# sch.net
KiCad netlist of a schematic drawn in EAGLE
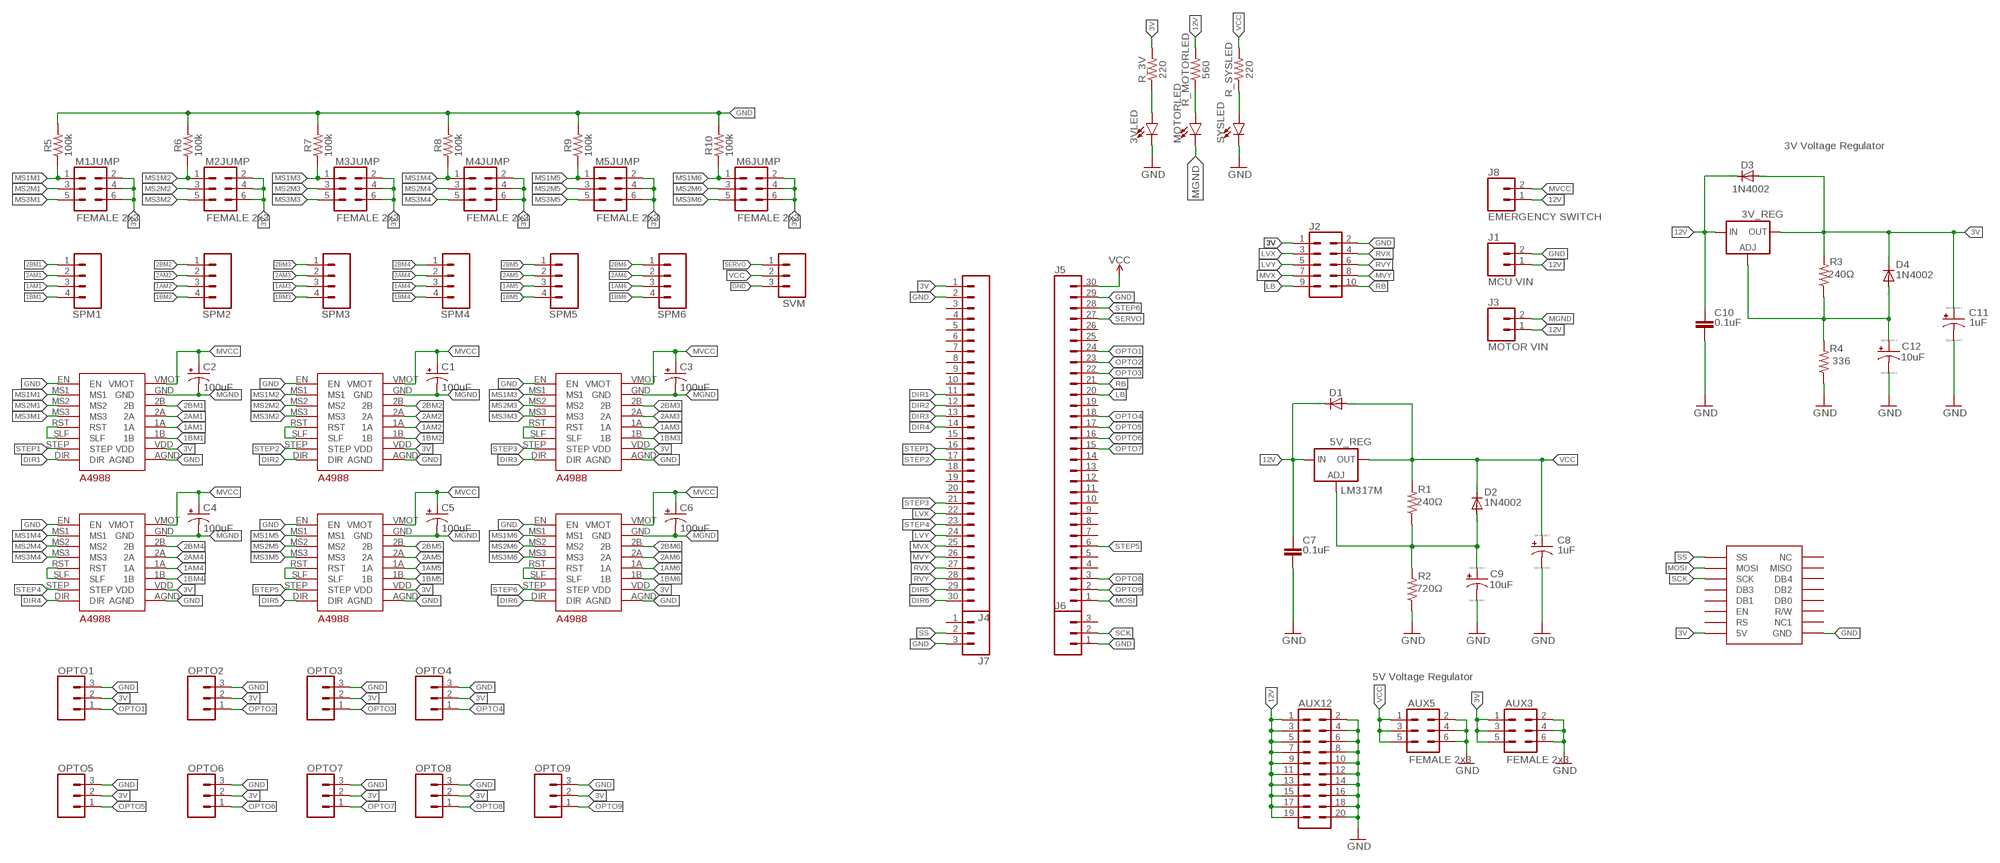
[diagram p0: schematic, sheet 1]

(export (version "E")
  (design (tool "Eeschema 10.0.6"))
  (components
    (comp (ref "3VLED")
      (value "LED1206")
      (footprint "eagle-import:LED-1206")
      (libsource (lib "eagle-import") (part "LED1206"))
    )
    (comp (ref "3V_REG")
      (value "LM317MBSTT3")
      (footprint "eagle-import:SOT223")
      (fields (field (name "PARTNUMBER") "LM317M"))
      (libsource (lib "eagle-import") (part "LM317?MBSTT3"))
    )
    (comp (ref "5V_REG")
      (value "LM317MBSTT3")
      (footprint "eagle-import:SOT223")
      (fields (field (name "PARTNUMBER") "LM317M"))
      (libsource (lib "eagle-import") (part "LM317?MBSTT3"))
    )
    (comp (ref "AUX3")
      (value "FEMALE 2x3")
      (footprint "eagle-import:2X3")
      (libsource (lib "eagle-import") (part "CONN_03X2FEMALE"))
    )
    (comp (ref "AUX5")
      (value "FEMALE 2x3")
      (footprint "eagle-import:2X3")
      (libsource (lib "eagle-import") (part "CONN_03X2FEMALE"))
    )
    (comp (ref "AUX12")
      (value "CONN_10X2")
      (footprint "eagle-import:2X10")
      (libsource (lib "eagle-import") (part "CONN_10X2"))
    )
    (comp (ref "C1")
      (value "100uF")
      (footprint "eagle-import:CPOL-RADIAL-2.5MM-6.5MM")
      (libsource (lib "eagle-import") (part "100UF-POLAR-RADIAL-2.5MM-25V-20%"))
    )
    (comp (ref "C2")
      (value "100uF")
      (footprint "eagle-import:CPOL-RADIAL-2.5MM-6.5MM")
      (libsource (lib "eagle-import") (part "100UF-POLAR-RADIAL-2.5MM-25V-20%"))
    )
    (comp (ref "C3")
      (value "100uF")
      (footprint "eagle-import:CPOL-RADIAL-2.5MM-6.5MM")
      (libsource (lib "eagle-import") (part "100UF-POLAR-RADIAL-2.5MM-25V-20%"))
    )
    (comp (ref "C4")
      (value "100uF")
      (footprint "eagle-import:CPOL-RADIAL-2.5MM-6.5MM")
      (libsource (lib "eagle-import") (part "100UF-POLAR-RADIAL-2.5MM-25V-20%"))
    )
    (comp (ref "C5")
      (value "100uF")
      (footprint "eagle-import:CPOL-RADIAL-2.5MM-6.5MM")
      (libsource (lib "eagle-import") (part "100UF-POLAR-RADIAL-2.5MM-25V-20%"))
    )
    (comp (ref "C6")
      (value "100uF")
      (footprint "eagle-import:CPOL-RADIAL-2.5MM-6.5MM")
      (libsource (lib "eagle-import") (part "100UF-POLAR-RADIAL-2.5MM-25V-20%"))
    )
    (comp (ref "C7")
      (value "0.1uF")
      (footprint "eagle-import:C075-052X106")
      (libsource (lib "eagle-import") (part "C-EU075-052X106"))
    )
    (comp (ref "C8")
      (value "1uF")
      (footprint "eagle-import:085CS_1AR")
      (libsource (lib "eagle-import") (part "CPOL-US085CS-1AR"))
    )
    (comp (ref "C9")
      (value "10uF")
      (footprint "eagle-import:085CS_1AR")
      (libsource (lib "eagle-import") (part "CPOL-US085CS-1AR"))
    )
    (comp (ref "C10")
      (value "0.1uF")
      (footprint "eagle-import:C075-052X106")
      (libsource (lib "eagle-import") (part "C-EU075-052X106"))
    )
    (comp (ref "C11")
      (value "1uF")
      (footprint "eagle-import:085CS_1AR")
      (libsource (lib "eagle-import") (part "CPOL-US085CS-1AR"))
    )
    (comp (ref "C12")
      (value "10uF")
      (footprint "eagle-import:085CS_1AR")
      (libsource (lib "eagle-import") (part "CPOL-US085CS-1AR"))
    )
    (comp (ref "D1")
      (value "1N4002")
      (footprint "eagle-import:DO41-10")
      (libsource (lib "eagle-import") (part "1N4004"))
    )
    (comp (ref "D2")
      (value "1N4002")
      (footprint "eagle-import:DO41-10")
      (libsource (lib "eagle-import") (part "1N4004"))
    )
    (comp (ref "D3")
      (value "1N4002")
      (footprint "eagle-import:DO41-10")
      (libsource (lib "eagle-import") (part "1N4004"))
    )
    (comp (ref "D4")
      (value "1N4002")
      (footprint "eagle-import:DO41-10")
      (libsource (lib "eagle-import") (part "1N4004"))
    )
    (comp (ref "J1")
      (value "MCU VIN")
      (footprint "eagle-import:SCREWTERMINAL-3.5MM-2")
      (libsource (lib "eagle-import") (part "CONN_023.5MM"))
    )
    (comp (ref "J2")
      (value "CONN_05X2SHD")
      (footprint "eagle-import:2X5-SHROUDED")
      (libsource (lib "eagle-import") (part "CONN_05X2SHD"))
    )
    (comp (ref "J3")
      (value "MOTOR VIN")
      (footprint "eagle-import:SCREWTERMINAL-3.5MM-2")
      (libsource (lib "eagle-import") (part "CONN_023.5MM"))
    )
    (comp (ref "J4")
      (value "CONN_30")
      (footprint "eagle-import:1X30")
      (libsource (lib "eagle-import") (part "CONN_30"))
    )
    (comp (ref "J5")
      (value "CONN_30")
      (footprint "eagle-import:1X30")
      (libsource (lib "eagle-import") (part "CONN_30"))
    )
    (comp (ref "J6")
      (value "CONN_03")
      (footprint "eagle-import:1X03")
      (libsource (lib "eagle-import") (part "SparkFun-Connectors_513_CONN_03"))
    )
    (comp (ref "J7")
      (value "CONN_03")
      (footprint "eagle-import:1X03")
      (libsource (lib "eagle-import") (part "SparkFun-Connectors_513_CONN_03"))
    )
    (comp (ref "J8")
      (value "EMERGENCY SWITCH")
      (footprint "eagle-import:SCREWTERMINAL-3.5MM-2")
      (libsource (lib "eagle-import") (part "CONN_023.5MM"))
    )
    (comp (ref "M1")
      (value "A4988_BREAK_OUTTROUGH_HOLE")
      (footprint "eagle-import:A4988_BREAK_OUT")
      (libsource (lib "eagle-import") (part "A4988_BREAK_OUTTROUGH_HOLE"))
    )
    (comp (ref "M1JUMP")
      (value "FEMALE 2x3")
      (footprint "eagle-import:2X3")
      (libsource (lib "eagle-import") (part "CONN_03X2FEMALE"))
    )
    (comp (ref "M2")
      (value "A4988_BREAK_OUTTROUGH_HOLE")
      (footprint "eagle-import:A4988_BREAK_OUT")
      (libsource (lib "eagle-import") (part "A4988_BREAK_OUTTROUGH_HOLE"))
    )
    (comp (ref "M2JUMP")
      (value "FEMALE 2x3")
      (footprint "eagle-import:2X3")
      (libsource (lib "eagle-import") (part "CONN_03X2FEMALE"))
    )
    (comp (ref "M3")
      (value "A4988_BREAK_OUTTROUGH_HOLE")
      (footprint "eagle-import:A4988_BREAK_OUT")
      (libsource (lib "eagle-import") (part "A4988_BREAK_OUTTROUGH_HOLE"))
    )
    (comp (ref "M3JUMP")
      (value "FEMALE 2x3")
      (footprint "eagle-import:2X3")
      (libsource (lib "eagle-import") (part "CONN_03X2FEMALE"))
    )
    (comp (ref "M4")
      (value "A4988_BREAK_OUTTROUGH_HOLE")
      (footprint "eagle-import:A4988_BREAK_OUT")
      (libsource (lib "eagle-import") (part "A4988_BREAK_OUTTROUGH_HOLE"))
    )
    (comp (ref "M4JUMP")
      (value "FEMALE 2x3")
      (footprint "eagle-import:2X3")
      (libsource (lib "eagle-import") (part "CONN_03X2FEMALE"))
    )
    (comp (ref "M5")
      (value "A4988_BREAK_OUTTROUGH_HOLE")
      (footprint "eagle-import:A4988_BREAK_OUT")
      (libsource (lib "eagle-import") (part "A4988_BREAK_OUTTROUGH_HOLE"))
    )
    (comp (ref "M5JUMP")
      (value "FEMALE 2x3")
      (footprint "eagle-import:2X3")
      (libsource (lib "eagle-import") (part "CONN_03X2FEMALE"))
    )
    (comp (ref "M6")
      (value "A4988_BREAK_OUTTROUGH_HOLE")
      (footprint "eagle-import:A4988_BREAK_OUT")
      (libsource (lib "eagle-import") (part "A4988_BREAK_OUTTROUGH_HOLE"))
    )
    (comp (ref "M6JUMP")
      (value "FEMALE 2x3")
      (footprint "eagle-import:2X3")
      (libsource (lib "eagle-import") (part "CONN_03X2FEMALE"))
    )
    (comp (ref "MOTORLED")
      (value "LED1206")
      (footprint "eagle-import:LED-1206")
      (libsource (lib "eagle-import") (part "LED1206"))
    )
    (comp (ref "OPTO1")
      (value "455-1750-1-ND")
      (footprint "eagle-import:1X03")
      (libsource (lib "eagle-import") (part "CONN_03"))
    )
    (comp (ref "OPTO2")
      (value "455-1750-1-ND")
      (footprint "eagle-import:1X03")
      (libsource (lib "eagle-import") (part "CONN_03"))
    )
    (comp (ref "OPTO3")
      (value "455-1750-1-ND")
      (footprint "eagle-import:1X03")
      (libsource (lib "eagle-import") (part "CONN_03"))
    )
    (comp (ref "OPTO4")
      (value "455-1750-1-ND")
      (footprint "eagle-import:1X03")
      (libsource (lib "eagle-import") (part "CONN_03"))
    )
    (comp (ref "OPTO5")
      (value "455-1750-1-ND")
      (footprint "eagle-import:1X03")
      (libsource (lib "eagle-import") (part "CONN_03"))
    )
    (comp (ref "OPTO6")
      (value "455-1750-1-ND")
      (footprint "eagle-import:1X03")
      (libsource (lib "eagle-import") (part "CONN_03"))
    )
    (comp (ref "OPTO7")
      (value "455-1750-1-ND")
      (footprint "eagle-import:1X03")
      (libsource (lib "eagle-import") (part "CONN_03"))
    )
    (comp (ref "OPTO8")
      (value "455-1750-1-ND")
      (footprint "eagle-import:1X03")
      (libsource (lib "eagle-import") (part "CONN_03"))
    )
    (comp (ref "OPTO9")
      (value "455-1750-1-ND")
      (footprint "eagle-import:1X03")
      (libsource (lib "eagle-import") (part "CONN_03"))
    )
    (comp (ref "R1")
      (value "240Ω")
      (footprint "eagle-import:M0805")
      (libsource (lib "eagle-import") (part "R-US_M0805"))
    )
    (comp (ref "R2")
      (value "720Ω")
      (footprint "eagle-import:M0805")
      (libsource (lib "eagle-import") (part "R-US_M0805"))
    )
    (comp (ref "R3")
      (value "240Ω")
      (footprint "eagle-import:M0805")
      (libsource (lib "eagle-import") (part "R-US_M0805"))
    )
    (comp (ref "R4")
      (value "336")
      (footprint "eagle-import:M0805")
      (libsource (lib "eagle-import") (part "R-US_M0805"))
    )
    (comp (ref "R5")
      (value "100k")
      (footprint "eagle-import:0603")
      (libsource (lib "eagle-import") (part "100KOHM-0603-1/10W-1%"))
    )
    (comp (ref "R6")
      (value "100k")
      (footprint "eagle-import:0603")
      (libsource (lib "eagle-import") (part "100KOHM-0603-1/10W-1%"))
    )
    (comp (ref "R7")
      (value "100k")
      (footprint "eagle-import:0603")
      (libsource (lib "eagle-import") (part "100KOHM-0603-1/10W-1%"))
    )
    (comp (ref "R8")
      (value "100k")
      (footprint "eagle-import:0603")
      (libsource (lib "eagle-import") (part "100KOHM-0603-1/10W-1%"))
    )
    (comp (ref "R9")
      (value "100k")
      (footprint "eagle-import:0603")
      (libsource (lib "eagle-import") (part "100KOHM-0603-1/10W-1%"))
    )
    (comp (ref "R10")
      (value "100k")
      (footprint "eagle-import:0603")
      (libsource (lib "eagle-import") (part "100KOHM-0603-1/10W-1%"))
    )
    (comp (ref "R_3V")
      (value "220")
      (footprint "eagle-import:0603")
      (libsource (lib "eagle-import") (part "680OHM-0603-1/10W-5%"))
    )
    (comp (ref "R_MOTORLED")
      (value "560")
      (footprint "eagle-import:0603")
      (libsource (lib "eagle-import") (part "680OHM-0603-1/10W-5%"))
    )
    (comp (ref "R_SYSLED")
      (value "220")
      (footprint "eagle-import:0603")
      (libsource (lib "eagle-import") (part "680OHM-0603-1/10W-5%"))
    )
    (comp (ref "SPM1")
      (value "CONN_04")
      (footprint "eagle-import:1X04")
      (libsource (lib "eagle-import") (part "CONN_04"))
    )
    (comp (ref "SPM2")
      (value "CONN_04")
      (footprint "eagle-import:1X04")
      (libsource (lib "eagle-import") (part "CONN_04"))
    )
    (comp (ref "SPM3")
      (value "CONN_04")
      (footprint "eagle-import:1X04")
      (libsource (lib "eagle-import") (part "CONN_04"))
    )
    (comp (ref "SPM4")
      (value "CONN_04")
      (footprint "eagle-import:1X04")
      (libsource (lib "eagle-import") (part "CONN_04"))
    )
    (comp (ref "SPM5")
      (value "CONN_04")
      (footprint "eagle-import:1X04")
      (libsource (lib "eagle-import") (part "CONN_04"))
    )
    (comp (ref "SPM6")
      (value "CONN_04")
      (footprint "eagle-import:1X04")
      (libsource (lib "eagle-import") (part "CONN_04"))
    )
    (comp (ref "SVM")
      (value "CONN_03")
      (footprint "eagle-import:1X03")
      (libsource (lib "eagle-import") (part "SparkFun-Connectors_513_CONN_03"))
    )
    (comp (ref "SYSLED")
      (value "LED1206")
      (footprint "eagle-import:LED-1206")
      (libsource (lib "eagle-import") (part "LED1206"))
    )
    (comp (ref "U$7")
      (value "LCD-BREAKOUT")
      (footprint "eagle-import:LCD_BREAKOUT")
      (libsource (lib "eagle-import") (part "LCD-BREAKOUT"))
    )
  )
  (nets
    (net (code "1") (name "1AM1") (class "Default")
      (node (ref "M1") (pin "1A") (pinfunction "1A_1A") (pintype "bidirectional"))
      (node (ref "SPM1") (pin "3") (pinfunction "3_3") (pintype "passive"))
    )
    (net (code "2") (name "1AM2") (class "Default")
      (node (ref "M2") (pin "1A") (pinfunction "1A_1A") (pintype "bidirectional"))
      (node (ref "SPM2") (pin "3") (pinfunction "3_3") (pintype "passive"))
    )
    (net (code "3") (name "1AM3") (class "Default")
      (node (ref "M3") (pin "1A") (pinfunction "1A_1A") (pintype "bidirectional"))
      (node (ref "SPM3") (pin "3") (pinfunction "3_3") (pintype "passive"))
    )
    (net (code "4") (name "1AM4") (class "Default")
      (node (ref "M4") (pin "1A") (pinfunction "1A_1A") (pintype "bidirectional"))
      (node (ref "SPM4") (pin "3") (pinfunction "3_3") (pintype "passive"))
    )
    (net (code "5") (name "1AM5") (class "Default")
      (node (ref "M5") (pin "1A") (pinfunction "1A_1A") (pintype "bidirectional"))
      (node (ref "SPM5") (pin "3") (pinfunction "3_3") (pintype "passive"))
    )
    (net (code "6") (name "1AM6") (class "Default")
      (node (ref "M6") (pin "1A") (pinfunction "1A_1A") (pintype "bidirectional"))
      (node (ref "SPM6") (pin "3") (pinfunction "3_3") (pintype "passive"))
    )
    (net (code "7") (name "1BM1") (class "Default")
      (node (ref "M1") (pin "1B") (pinfunction "1B_1B") (pintype "bidirectional"))
      (node (ref "SPM1") (pin "4") (pinfunction "4_4") (pintype "passive"))
    )
    (net (code "8") (name "1BM2") (class "Default")
      (node (ref "M2") (pin "1B") (pinfunction "1B_1B") (pintype "bidirectional"))
      (node (ref "SPM2") (pin "4") (pinfunction "4_4") (pintype "passive"))
    )
    (net (code "9") (name "1BM3") (class "Default")
      (node (ref "M3") (pin "1B") (pinfunction "1B_1B") (pintype "bidirectional"))
      (node (ref "SPM3") (pin "4") (pinfunction "4_4") (pintype "passive"))
    )
    (net (code "10") (name "1BM4") (class "Default")
      (node (ref "M4") (pin "1B") (pinfunction "1B_1B") (pintype "bidirectional"))
      (node (ref "SPM4") (pin "4") (pinfunction "4_4") (pintype "passive"))
    )
    (net (code "11") (name "1BM5") (class "Default")
      (node (ref "M5") (pin "1B") (pinfunction "1B_1B") (pintype "bidirectional"))
      (node (ref "SPM5") (pin "4") (pinfunction "4_4") (pintype "passive"))
    )
    (net (code "12") (name "1BM6") (class "Default")
      (node (ref "M6") (pin "1B") (pinfunction "1B_1B") (pintype "bidirectional"))
      (node (ref "SPM6") (pin "4") (pinfunction "4_4") (pintype "passive"))
    )
    (net (code "13") (name "2AM1") (class "Default")
      (node (ref "M1") (pin "2A") (pinfunction "2A_2A") (pintype "bidirectional"))
      (node (ref "SPM1") (pin "2") (pinfunction "2_2") (pintype "passive"))
    )
    (net (code "14") (name "2AM2") (class "Default")
      (node (ref "M2") (pin "2A") (pinfunction "2A_2A") (pintype "bidirectional"))
      (node (ref "SPM2") (pin "2") (pinfunction "2_2") (pintype "passive"))
    )
    (net (code "15") (name "2AM3") (class "Default")
      (node (ref "M3") (pin "2A") (pinfunction "2A_2A") (pintype "bidirectional"))
      (node (ref "SPM3") (pin "2") (pinfunction "2_2") (pintype "passive"))
    )
    (net (code "16") (name "2AM4") (class "Default")
      (node (ref "M4") (pin "2A") (pinfunction "2A_2A") (pintype "bidirectional"))
      (node (ref "SPM4") (pin "2") (pinfunction "2_2") (pintype "passive"))
    )
    (net (code "17") (name "2AM5") (class "Default")
      (node (ref "M5") (pin "2A") (pinfunction "2A_2A") (pintype "bidirectional"))
      (node (ref "SPM5") (pin "2") (pinfunction "2_2") (pintype "passive"))
    )
    (net (code "18") (name "2AM6") (class "Default")
      (node (ref "M6") (pin "2A") (pinfunction "2A_2A") (pintype "bidirectional"))
      (node (ref "SPM6") (pin "2") (pinfunction "2_2") (pintype "passive"))
    )
    (net (code "19") (name "2BM1") (class "Default")
      (node (ref "M1") (pin "2B") (pinfunction "2B_2B") (pintype "bidirectional"))
      (node (ref "SPM1") (pin "1") (pinfunction "1_1") (pintype "passive"))
    )
    (net (code "20") (name "2BM2") (class "Default")
      (node (ref "M2") (pin "2B") (pinfunction "2B_2B") (pintype "bidirectional"))
      (node (ref "SPM2") (pin "1") (pinfunction "1_1") (pintype "passive"))
    )
    (net (code "21") (name "2BM3") (class "Default")
      (node (ref "M3") (pin "2B") (pinfunction "2B_2B") (pintype "bidirectional"))
      (node (ref "SPM3") (pin "1") (pinfunction "1_1") (pintype "passive"))
    )
    (net (code "22") (name "2BM4") (class "Default")
      (node (ref "M4") (pin "2B") (pinfunction "2B_2B") (pintype "bidirectional"))
      (node (ref "SPM4") (pin "1") (pinfunction "1_1") (pintype "passive"))
    )
    (net (code "23") (name "2BM5") (class "Default")
      (node (ref "M5") (pin "2B") (pinfunction "2B_2B") (pintype "bidirectional"))
      (node (ref "SPM5") (pin "1") (pinfunction "1_1") (pintype "passive"))
    )
    (net (code "24") (name "2BM6") (class "Default")
      (node (ref "M6") (pin "2B") (pinfunction "2B_2B") (pintype "bidirectional"))
      (node (ref "SPM6") (pin "1") (pinfunction "1_1") (pintype "passive"))
    )
    (net (code "25") (name "3V") (class "Default")
      (node (ref "3V_REG") (pin "4") (pinfunction "OUT_4") (pintype "passive"))
      (node (ref "AUX3") (pin "1") (pinfunction "1_1") (pintype "bidirectional"))
      (node (ref "AUX3") (pin "3") (pinfunction "3_3") (pintype "bidirectional"))
      (node (ref "AUX3") (pin "5") (pinfunction "5_5") (pintype "bidirectional"))
      (node (ref "C11") (pin "+") (pinfunction "+_+") (pintype "passive"))
      (node (ref "D3") (pin "A") (pinfunction "A_A") (pintype "passive"))
      (node (ref "D4") (pin "C") (pinfunction "C_C") (pintype "passive"))
      (node (ref "J2") (pin "1") (pinfunction "1_1") (pintype "passive"))
      (node (ref "J4") (pin "1") (pinfunction "1_1") (pintype "passive"))
      (node (ref "M1") (pin "VDD") (pinfunction "VDD_VDD") (pintype "bidirectional"))
      (node (ref "M1JUMP") (pin "2") (pinfunction "2_2") (pintype "bidirectional"))
      (node (ref "M1JUMP") (pin "4") (pinfunction "4_4") (pintype "bidirectional"))
      (node (ref "M1JUMP") (pin "6") (pinfunction "6_6") (pintype "bidirectional"))
      (node (ref "M2") (pin "VDD") (pinfunction "VDD_VDD") (pintype "bidirectional"))
      (node (ref "M2JUMP") (pin "2") (pinfunction "2_2") (pintype "bidirectional"))
      (node (ref "M2JUMP") (pin "4") (pinfunction "4_4") (pintype "bidirectional"))
      (node (ref "M2JUMP") (pin "6") (pinfunction "6_6") (pintype "bidirectional"))
      (node (ref "M3") (pin "VDD") (pinfunction "VDD_VDD") (pintype "bidirectional"))
      (node (ref "M3JUMP") (pin "2") (pinfunction "2_2") (pintype "bidirectional"))
      (node (ref "M3JUMP") (pin "4") (pinfunction "4_4") (pintype "bidirectional"))
      (node (ref "M3JUMP") (pin "6") (pinfunction "6_6") (pintype "bidirectional"))
      (node (ref "M4") (pin "VDD") (pinfunction "VDD_VDD") (pintype "bidirectional"))
      (node (ref "M4JUMP") (pin "2") (pinfunction "2_2") (pintype "bidirectional"))
      (node (ref "M4JUMP") (pin "4") (pinfunction "4_4") (pintype "bidirectional"))
      (node (ref "M4JUMP") (pin "6") (pinfunction "6_6") (pintype "bidirectional"))
      (node (ref "M5") (pin "VDD") (pinfunction "VDD_VDD") (pintype "bidirectional"))
      (node (ref "M5JUMP") (pin "2") (pinfunction "2_2") (pintype "bidirectional"))
      (node (ref "M5JUMP") (pin "4") (pinfunction "4_4") (pintype "bidirectional"))
      (node (ref "M5JUMP") (pin "6") (pinfunction "6_6") (pintype "bidirectional"))
      (node (ref "M6") (pin "VDD") (pinfunction "VDD_VDD") (pintype "bidirectional"))
      (node (ref "M6JUMP") (pin "2") (pinfunction "2_2") (pintype "bidirectional"))
      (node (ref "M6JUMP") (pin "4") (pinfunction "4_4") (pintype "bidirectional"))
      (node (ref "M6JUMP") (pin "6") (pinfunction "6_6") (pintype "bidirectional"))
      (node (ref "OPTO1") (pin "2") (pinfunction "2_2") (pintype "passive"))
      (node (ref "OPTO2") (pin "2") (pinfunction "2_2") (pintype "passive"))
      (node (ref "OPTO3") (pin "2") (pinfunction "2_2") (pintype "passive"))
      (node (ref "OPTO4") (pin "2") (pinfunction "2_2") (pintype "passive"))
      (node (ref "OPTO5") (pin "2") (pinfunction "2_2") (pintype "passive"))
      (node (ref "OPTO6") (pin "2") (pinfunction "2_2") (pintype "passive"))
      (node (ref "OPTO7") (pin "2") (pinfunction "2_2") (pintype "passive"))
      (node (ref "OPTO8") (pin "2") (pinfunction "2_2") (pintype "passive"))
      (node (ref "OPTO9") (pin "2") (pinfunction "2_2") (pintype "passive"))
      (node (ref "R3") (pin "2") (pinfunction "2_2") (pintype "passive"))
      (node (ref "R_3V") (pin "2") (pinfunction "2_2") (pintype "passive"))
      (node (ref "U$7") (pin "P$2") (pinfunction "5V_P$2") (pintype "bidirectional"))
    )
    (net (code "26") (name "12V") (class "Default")
      (node (ref "3V_REG") (pin "3") (pinfunction "IN_3") (pintype "input"))
      (node (ref "5V_REG") (pin "3") (pinfunction "IN_3") (pintype "input"))
      (node (ref "AUX12") (pin "1") (pinfunction "1_1") (pintype "passive"))
      (node (ref "AUX12") (pin "11") (pinfunction "11_11") (pintype "passive"))
      (node (ref "AUX12") (pin "13") (pinfunction "13_13") (pintype "passive"))
      (node (ref "AUX12") (pin "15") (pinfunction "15_15") (pintype "passive"))
      (node (ref "AUX12") (pin "17") (pinfunction "17_17") (pintype "passive"))
      (node (ref "AUX12") (pin "19") (pinfunction "19_19") (pintype "passive"))
      (node (ref "AUX12") (pin "3") (pinfunction "3_3") (pintype "passive"))
      (node (ref "AUX12") (pin "5") (pinfunction "5_5") (pintype "passive"))
      (node (ref "AUX12") (pin "7") (pinfunction "7_7") (pintype "passive"))
      (node (ref "AUX12") (pin "9") (pinfunction "9_9") (pintype "passive"))
      (node (ref "C10") (pin "1") (pinfunction "1_1") (pintype "passive"))
      (node (ref "C7") (pin "1") (pinfunction "1_1") (pintype "passive"))
      (node (ref "D1") (pin "C") (pinfunction "C_C") (pintype "passive"))
      (node (ref "D3") (pin "C") (pinfunction "C_C") (pintype "passive"))
      (node (ref "J1") (pin "1") (pinfunction "1_1") (pintype "passive"))
      (node (ref "J3") (pin "1") (pinfunction "1_1") (pintype "passive"))
      (node (ref "J8") (pin "1") (pinfunction "1_1") (pintype "passive"))
      (node (ref "R_MOTORLED") (pin "2") (pinfunction "2_2") (pintype "passive"))
    )
    (net (code "27") (name "DIR1") (class "Default")
      (node (ref "J4") (pin "11") (pinfunction "11_11") (pintype "passive"))
      (node (ref "M1") (pin "DIR") (pinfunction "DIR_DIR") (pintype "bidirectional"))
    )
    (net (code "28") (name "DIR2") (class "Default")
      (node (ref "J4") (pin "12") (pinfunction "12_12") (pintype "passive"))
      (node (ref "M2") (pin "DIR") (pinfunction "DIR_DIR") (pintype "bidirectional"))
    )
    (net (code "29") (name "DIR3") (class "Default")
      (node (ref "J4") (pin "13") (pinfunction "13_13") (pintype "passive"))
      (node (ref "M3") (pin "DIR") (pinfunction "DIR_DIR") (pintype "bidirectional"))
    )
    (net (code "30") (name "DIR4") (class "Default")
      (node (ref "J4") (pin "14") (pinfunction "14_14") (pintype "passive"))
      (node (ref "M4") (pin "DIR") (pinfunction "DIR_DIR") (pintype "bidirectional"))
    )
    (net (code "31") (name "DIR5") (class "Default")
      (node (ref "J4") (pin "29") (pinfunction "29_29") (pintype "passive"))
      (node (ref "M5") (pin "DIR") (pinfunction "DIR_DIR") (pintype "bidirectional"))
    )
    (net (code "32") (name "DIR6") (class "Default")
      (node (ref "J4") (pin "30") (pinfunction "30_30") (pintype "passive"))
      (node (ref "M6") (pin "DIR") (pinfunction "DIR_DIR") (pintype "bidirectional"))
    )
    (net (code "33") (name "GND") (class "Default")
      (node (ref "3VLED") (pin "C") (pinfunction "C_C") (pintype "passive"))
      (node (ref "AUX12") (pin "10") (pinfunction "10_10") (pintype "passive"))
      (node (ref "AUX12") (pin "12") (pinfunction "12_12") (pintype "passive"))
      (node (ref "AUX12") (pin "14") (pinfunction "14_14") (pintype "passive"))
      (node (ref "AUX12") (pin "16") (pinfunction "16_16") (pintype "passive"))
      (node (ref "AUX12") (pin "18") (pinfunction "18_18") (pintype "passive"))
      (node (ref "AUX12") (pin "2") (pinfunction "2_2") (pintype "passive"))
      (node (ref "AUX12") (pin "20") (pinfunction "20_20") (pintype "passive"))
      (node (ref "AUX12") (pin "4") (pinfunction "4_4") (pintype "passive"))
      (node (ref "AUX12") (pin "6") (pinfunction "6_6") (pintype "passive"))
      (node (ref "AUX12") (pin "8") (pinfunction "8_8") (pintype "passive"))
      (node (ref "AUX3") (pin "2") (pinfunction "2_2") (pintype "bidirectional"))
      (node (ref "AUX3") (pin "4") (pinfunction "4_4") (pintype "bidirectional"))
      (node (ref "AUX3") (pin "6") (pinfunction "6_6") (pintype "bidirectional"))
      (node (ref "AUX5") (pin "2") (pinfunction "2_2") (pintype "bidirectional"))
      (node (ref "AUX5") (pin "4") (pinfunction "4_4") (pintype "bidirectional"))
      (node (ref "AUX5") (pin "6") (pinfunction "6_6") (pintype "bidirectional"))
      (node (ref "C10") (pin "2") (pinfunction "2_2") (pintype "passive"))
      (node (ref "C11") (pin "-") (pinfunction "-_-") (pintype "passive"))
      (node (ref "C12") (pin "-") (pinfunction "-_-") (pintype "passive"))
      (node (ref "C7") (pin "2") (pinfunction "2_2") (pintype "passive"))
      (node (ref "C8") (pin "-") (pinfunction "-_-") (pintype "passive"))
      (node (ref "C9") (pin "-") (pinfunction "-_-") (pintype "passive"))
      (node (ref "J1") (pin "2") (pinfunction "2_2") (pintype "passive"))
      (node (ref "J2") (pin "2") (pinfunction "2_2") (pintype "passive"))
      (node (ref "J4") (pin "2") (pinfunction "2_2") (pintype "passive"))
      (node (ref "J5") (pin "29") (pinfunction "29_29") (pintype "passive"))
      (node (ref "J6") (pin "1") (pinfunction "1_1") (pintype "passive"))
      (node (ref "J7") (pin "3") (pinfunction "3_3") (pintype "passive"))
      (node (ref "M1") (pin "AGND") (pinfunction "AGND_AGND") (pintype "bidirectional"))
      (node (ref "M1") (pin "EN") (pinfunction "EN_EN") (pintype "bidirectional"))
      (node (ref "M2") (pin "AGND") (pinfunction "AGND_AGND") (pintype "bidirectional"))
      (node (ref "M2") (pin "EN") (pinfunction "EN_EN") (pintype "bidirectional"))
      (node (ref "M3") (pin "AGND") (pinfunction "AGND_AGND") (pintype "bidirectional"))
      (node (ref "M3") (pin "EN") (pinfunction "EN_EN") (pintype "bidirectional"))
      (node (ref "M4") (pin "AGND") (pinfunction "AGND_AGND") (pintype "bidirectional"))
      (node (ref "M4") (pin "EN") (pinfunction "EN_EN") (pintype "bidirectional"))
      (node (ref "M5") (pin "AGND") (pinfunction "AGND_AGND") (pintype "bidirectional"))
      (node (ref "M5") (pin "EN") (pinfunction "EN_EN") (pintype "bidirectional"))
      (node (ref "M6") (pin "AGND") (pinfunction "AGND_AGND") (pintype "bidirectional"))
      (node (ref "M6") (pin "EN") (pinfunction "EN_EN") (pintype "bidirectional"))
      (node (ref "OPTO1") (pin "3") (pinfunction "3_3") (pintype "passive"))
      (node (ref "OPTO2") (pin "3") (pinfunction "3_3") (pintype "passive"))
      (node (ref "OPTO3") (pin "3") (pinfunction "3_3") (pintype "passive"))
      (node (ref "OPTO4") (pin "3") (pinfunction "3_3") (pintype "passive"))
      (node (ref "OPTO5") (pin "3") (pinfunction "3_3") (pintype "passive"))
      (node (ref "OPTO6") (pin "3") (pinfunction "3_3") (pintype "passive"))
      (node (ref "OPTO7") (pin "3") (pinfunction "3_3") (pintype "passive"))
      (node (ref "OPTO8") (pin "3") (pinfunction "3_3") (pintype "passive"))
      (node (ref "OPTO9") (pin "3") (pinfunction "3_3") (pintype "passive"))
      (node (ref "R10") (pin "2") (pinfunction "2_2") (pintype "passive"))
      (node (ref "R2") (pin "1") (pinfunction "1_1") (pintype "passive"))
      (node (ref "R4") (pin "1") (pinfunction "1_1") (pintype "passive"))
      (node (ref "R5") (pin "2") (pinfunction "2_2") (pintype "passive"))
      (node (ref "R6") (pin "2") (pinfunction "2_2") (pintype "passive"))
      (node (ref "R7") (pin "2") (pinfunction "2_2") (pintype "passive"))
      (node (ref "R8") (pin "2") (pinfunction "2_2") (pintype "passive"))
      (node (ref "R9") (pin "2") (pinfunction "2_2") (pintype "passive"))
      (node (ref "SVM") (pin "3") (pinfunction "3_3") (pintype "passive"))
      (node (ref "SYSLED") (pin "C") (pinfunction "C_C") (pintype "passive"))
      (node (ref "U$7") (pin "P$1") (pinfunction "GND_P$1") (pintype "bidirectional"))
    )
    (net (code "34") (name "LB") (class "Default")
      (node (ref "J2") (pin "9") (pinfunction "9_9") (pintype "passive"))
      (node (ref "J5") (pin "20") (pinfunction "20_20") (pintype "passive"))
    )
    (net (code "35") (name "LVX") (class "Default")
      (node (ref "J2") (pin "3") (pinfunction "3_3") (pintype "passive"))
      (node (ref "J4") (pin "22") (pinfunction "22_22") (pintype "passive"))
    )
    (net (code "36") (name "LVY") (class "Default")
      (node (ref "J2") (pin "5") (pinfunction "5_5") (pintype "passive"))
      (node (ref "J4") (pin "24") (pinfunction "24_24") (pintype "passive"))
    )
    (net (code "37") (name "MGND") (class "Default")
      (node (ref "C1") (pin "2") (pinfunction "-_2") (pintype "passive"))
      (node (ref "C2") (pin "2") (pinfunction "-_2") (pintype "passive"))
      (node (ref "C3") (pin "2") (pinfunction "-_2") (pintype "passive"))
      (node (ref "C4") (pin "2") (pinfunction "-_2") (pintype "passive"))
      (node (ref "C5") (pin "2") (pinfunction "-_2") (pintype "passive"))
      (node (ref "C6") (pin "2") (pinfunction "-_2") (pintype "passive"))
      (node (ref "J3") (pin "2") (pinfunction "2_2") (pintype "passive"))
      (node (ref "M1") (pin "GND") (pinfunction "GND_GND") (pintype "bidirectional"))
      (node (ref "M2") (pin "GND") (pinfunction "GND_GND") (pintype "bidirectional"))
      (node (ref "M3") (pin "GND") (pinfunction "GND_GND") (pintype "bidirectional"))
      (node (ref "M4") (pin "GND") (pinfunction "GND_GND") (pintype "bidirectional"))
      (node (ref "M5") (pin "GND") (pinfunction "GND_GND") (pintype "bidirectional"))
      (node (ref "M6") (pin "GND") (pinfunction "GND_GND") (pintype "bidirectional"))
      (node (ref "MOTORLED") (pin "C") (pinfunction "C_C") (pintype "passive"))
    )
    (net (code "38") (name "MOSI") (class "Default")
      (node (ref "J5") (pin "1") (pinfunction "1_1") (pintype "passive"))
      (node (ref "U$7") (pin "P$14") (pinfunction "MOSI_P$14") (pintype "bidirectional"))
    )
    (net (code "39") (name "MS1M1") (class "Default")
      (node (ref "M1") (pin "MS1") (pinfunction "MS1_MS1") (pintype "bidirectional"))
      (node (ref "M1JUMP") (pin "1") (pinfunction "1_1") (pintype "bidirectional"))
      (node (ref "R5") (pin "1") (pinfunction "1_1") (pintype "passive"))
    )
    (net (code "40") (name "MS1M2") (class "Default")
      (node (ref "M2") (pin "MS1") (pinfunction "MS1_MS1") (pintype "bidirectional"))
      (node (ref "M2JUMP") (pin "1") (pinfunction "1_1") (pintype "bidirectional"))
      (node (ref "R6") (pin "1") (pinfunction "1_1") (pintype "passive"))
    )
    (net (code "41") (name "MS1M3") (class "Default")
      (node (ref "M3") (pin "MS1") (pinfunction "MS1_MS1") (pintype "bidirectional"))
      (node (ref "M3JUMP") (pin "1") (pinfunction "1_1") (pintype "bidirectional"))
      (node (ref "R7") (pin "1") (pinfunction "1_1") (pintype "passive"))
    )
    (net (code "42") (name "MS1M4") (class "Default")
      (node (ref "M4") (pin "MS1") (pinfunction "MS1_MS1") (pintype "bidirectional"))
      (node (ref "M4JUMP") (pin "1") (pinfunction "1_1") (pintype "bidirectional"))
      (node (ref "R8") (pin "1") (pinfunction "1_1") (pintype "passive"))
    )
    (net (code "43") (name "MS1M5") (class "Default")
      (node (ref "M5") (pin "MS1") (pinfunction "MS1_MS1") (pintype "bidirectional"))
      (node (ref "M5JUMP") (pin "1") (pinfunction "1_1") (pintype "bidirectional"))
      (node (ref "R9") (pin "1") (pinfunction "1_1") (pintype "passive"))
    )
    (net (code "44") (name "MS1M6") (class "Default")
      (node (ref "M6") (pin "MS1") (pinfunction "MS1_MS1") (pintype "bidirectional"))
      (node (ref "M6JUMP") (pin "1") (pinfunction "1_1") (pintype "bidirectional"))
      (node (ref "R10") (pin "1") (pinfunction "1_1") (pintype "passive"))
    )
    (net (code "45") (name "MS2M1") (class "Default")
      (node (ref "M1") (pin "MS2") (pinfunction "MS2_MS2") (pintype "bidirectional"))
      (node (ref "M1JUMP") (pin "3") (pinfunction "3_3") (pintype "bidirectional"))
    )
    (net (code "46") (name "MS2M2") (class "Default")
      (node (ref "M2") (pin "MS2") (pinfunction "MS2_MS2") (pintype "bidirectional"))
      (node (ref "M2JUMP") (pin "3") (pinfunction "3_3") (pintype "bidirectional"))
    )
    (net (code "47") (name "MS2M3") (class "Default")
      (node (ref "M3") (pin "MS2") (pinfunction "MS2_MS2") (pintype "bidirectional"))
      (node (ref "M3JUMP") (pin "3") (pinfunction "3_3") (pintype "bidirectional"))
    )
    (net (code "48") (name "MS2M4") (class "Default")
      (node (ref "M4") (pin "MS2") (pinfunction "MS2_MS2") (pintype "bidirectional"))
      (node (ref "M4JUMP") (pin "3") (pinfunction "3_3") (pintype "bidirectional"))
    )
    (net (code "49") (name "MS2M5") (class "Default")
      (node (ref "M5") (pin "MS2") (pinfunction "MS2_MS2") (pintype "bidirectional"))
      (node (ref "M5JUMP") (pin "3") (pinfunction "3_3") (pintype "bidirectional"))
    )
    (net (code "50") (name "MS2M6") (class "Default")
      (node (ref "M6") (pin "MS2") (pinfunction "MS2_MS2") (pintype "bidirectional"))
      (node (ref "M6JUMP") (pin "3") (pinfunction "3_3") (pintype "bidirectional"))
    )
    (net (code "51") (name "MS3M1") (class "Default")
      (node (ref "M1") (pin "MS3") (pinfunction "MS3_MS3") (pintype "bidirectional"))
      (node (ref "M1JUMP") (pin "5") (pinfunction "5_5") (pintype "bidirectional"))
    )
    (net (code "52") (name "MS3M2") (class "Default")
      (node (ref "M2") (pin "MS3") (pinfunction "MS3_MS3") (pintype "bidirectional"))
      (node (ref "M2JUMP") (pin "5") (pinfunction "5_5") (pintype "bidirectional"))
    )
    (net (code "53") (name "MS3M3") (class "Default")
      (node (ref "M3") (pin "MS3") (pinfunction "MS3_MS3") (pintype "bidirectional"))
      (node (ref "M3JUMP") (pin "5") (pinfunction "5_5") (pintype "bidirectional"))
    )
    (net (code "54") (name "MS3M4") (class "Default")
      (node (ref "M4") (pin "MS3") (pinfunction "MS3_MS3") (pintype "bidirectional"))
      (node (ref "M4JUMP") (pin "5") (pinfunction "5_5") (pintype "bidirectional"))
    )
    (net (code "55") (name "MS3M5") (class "Default")
      (node (ref "M5") (pin "MS3") (pinfunction "MS3_MS3") (pintype "bidirectional"))
      (node (ref "M5JUMP") (pin "5") (pinfunction "5_5") (pintype "bidirectional"))
    )
    (net (code "56") (name "MS3M6") (class "Default")
      (node (ref "M6") (pin "MS3") (pinfunction "MS3_MS3") (pintype "bidirectional"))
      (node (ref "M6JUMP") (pin "5") (pinfunction "5_5") (pintype "bidirectional"))
    )
    (net (code "57") (name "MVCC") (class "Default")
      (node (ref "C1") (pin "1") (pinfunction "+_1") (pintype "passive"))
      (node (ref "C2") (pin "1") (pinfunction "+_1") (pintype "passive"))
      (node (ref "C3") (pin "1") (pinfunction "+_1") (pintype "passive"))
      (node (ref "C4") (pin "1") (pinfunction "+_1") (pintype "passive"))
      (node (ref "C5") (pin "1") (pinfunction "+_1") (pintype "passive"))
      (node (ref "C6") (pin "1") (pinfunction "+_1") (pintype "passive"))
      (node (ref "J8") (pin "2") (pinfunction "2_2") (pintype "passive"))
      (node (ref "M1") (pin "VMOT") (pinfunction "VMOT_VMOT") (pintype "bidirectional"))
      (node (ref "M2") (pin "VMOT") (pinfunction "VMOT_VMOT") (pintype "bidirectional"))
      (node (ref "M3") (pin "VMOT") (pinfunction "VMOT_VMOT") (pintype "bidirectional"))
      (node (ref "M4") (pin "VMOT") (pinfunction "VMOT_VMOT") (pintype "bidirectional"))
      (node (ref "M5") (pin "VMOT") (pinfunction "VMOT_VMOT") (pintype "bidirectional"))
      (node (ref "M6") (pin "VMOT") (pinfunction "VMOT_VMOT") (pintype "bidirectional"))
    )
    (net (code "58") (name "MVX") (class "Default")
      (node (ref "J2") (pin "7") (pinfunction "7_7") (pintype "passive"))
      (node (ref "J4") (pin "25") (pinfunction "25_25") (pintype "passive"))
    )
    (net (code "59") (name "MVY") (class "Default")
      (node (ref "J2") (pin "8") (pinfunction "8_8") (pintype "passive"))
      (node (ref "J4") (pin "26") (pinfunction "26_26") (pintype "passive"))
    )
    (net (code "60") (name "Net-(3VLED-PadA)") (class "Default")
      (node (ref "3VLED") (pin "A") (pinfunction "A_A") (pintype "passive"))
      (node (ref "R_3V") (pin "1") (pinfunction "1_1") (pintype "passive"))
    )
    (net (code "61") (name "Net-(3V_REG-ADJ)") (class "Default")
      (node (ref "3V_REG") (pin "1") (pinfunction "ADJ_1") (pintype "input"))
      (node (ref "C12") (pin "+") (pinfunction "+_+") (pintype "passive"))
      (node (ref "D4") (pin "A") (pinfunction "A_A") (pintype "passive"))
      (node (ref "R3") (pin "1") (pinfunction "1_1") (pintype "passive"))
      (node (ref "R4") (pin "2") (pinfunction "2_2") (pintype "passive"))
    )
    (net (code "62") (name "Net-(5V_REG-ADJ)") (class "Default")
      (node (ref "5V_REG") (pin "1") (pinfunction "ADJ_1") (pintype "input"))
      (node (ref "C9") (pin "+") (pinfunction "+_+") (pintype "passive"))
      (node (ref "D2") (pin "A") (pinfunction "A_A") (pintype "passive"))
      (node (ref "R1") (pin "1") (pinfunction "1_1") (pintype "passive"))
      (node (ref "R2") (pin "2") (pinfunction "2_2") (pintype "passive"))
    )
    (net (code "63") (name "Net-(M1-PadRST)") (class "Default")
      (node (ref "M1") (pin "RST") (pinfunction "RST_RST") (pintype "bidirectional"))
      (node (ref "M1") (pin "SLF") (pinfunction "SLF_SLF") (pintype "bidirectional"))
    )
    (net (code "64") (name "Net-(M2-PadRST)") (class "Default")
      (node (ref "M2") (pin "RST") (pinfunction "RST_RST") (pintype "bidirectional"))
      (node (ref "M2") (pin "SLF") (pinfunction "SLF_SLF") (pintype "bidirectional"))
    )
    (net (code "65") (name "Net-(M3-PadRST)") (class "Default")
      (node (ref "M3") (pin "RST") (pinfunction "RST_RST") (pintype "bidirectional"))
      (node (ref "M3") (pin "SLF") (pinfunction "SLF_SLF") (pintype "bidirectional"))
    )
    (net (code "66") (name "Net-(M4-PadRST)") (class "Default")
      (node (ref "M4") (pin "RST") (pinfunction "RST_RST") (pintype "bidirectional"))
      (node (ref "M4") (pin "SLF") (pinfunction "SLF_SLF") (pintype "bidirectional"))
    )
    (net (code "67") (name "Net-(M5-PadRST)") (class "Default")
      (node (ref "M5") (pin "RST") (pinfunction "RST_RST") (pintype "bidirectional"))
      (node (ref "M5") (pin "SLF") (pinfunction "SLF_SLF") (pintype "bidirectional"))
    )
    (net (code "68") (name "Net-(M6-PadRST)") (class "Default")
      (node (ref "M6") (pin "RST") (pinfunction "RST_RST") (pintype "bidirectional"))
      (node (ref "M6") (pin "SLF") (pinfunction "SLF_SLF") (pintype "bidirectional"))
    )
    (net (code "69") (name "Net-(MOTORLED-PadA)") (class "Default")
      (node (ref "MOTORLED") (pin "A") (pinfunction "A_A") (pintype "passive"))
      (node (ref "R_MOTORLED") (pin "1") (pinfunction "1_1") (pintype "passive"))
    )
    (net (code "70") (name "Net-(R_SYSLED-Pad1)") (class "Default")
      (node (ref "R_SYSLED") (pin "1") (pinfunction "1_1") (pintype "passive"))
      (node (ref "SYSLED") (pin "A") (pinfunction "A_A") (pintype "passive"))
    )
    (net (code "71") (name "OPTO1") (class "Default")
      (node (ref "J5") (pin "24") (pinfunction "24_24") (pintype "passive"))
      (node (ref "OPTO1") (pin "1") (pinfunction "1_1") (pintype "passive"))
    )
    (net (code "72") (name "OPTO2") (class "Default")
      (node (ref "J5") (pin "23") (pinfunction "23_23") (pintype "passive"))
      (node (ref "OPTO2") (pin "1") (pinfunction "1_1") (pintype "passive"))
    )
    (net (code "73") (name "OPTO3") (class "Default")
      (node (ref "J5") (pin "22") (pinfunction "22_22") (pintype "passive"))
      (node (ref "OPTO3") (pin "1") (pinfunction "1_1") (pintype "passive"))
    )
    (net (code "74") (name "OPTO4") (class "Default")
      (node (ref "J5") (pin "18") (pinfunction "18_18") (pintype "passive"))
      (node (ref "OPTO4") (pin "1") (pinfunction "1_1") (pintype "passive"))
    )
    (net (code "75") (name "OPTO5") (class "Default")
      (node (ref "J5") (pin "17") (pinfunction "17_17") (pintype "passive"))
      (node (ref "OPTO5") (pin "1") (pinfunction "1_1") (pintype "passive"))
    )
    (net (code "76") (name "OPTO6") (class "Default")
      (node (ref "J5") (pin "16") (pinfunction "16_16") (pintype "passive"))
      (node (ref "OPTO6") (pin "1") (pinfunction "1_1") (pintype "passive"))
    )
    (net (code "77") (name "OPTO7") (class "Default")
      (node (ref "J5") (pin "15") (pinfunction "15_15") (pintype "passive"))
      (node (ref "OPTO7") (pin "1") (pinfunction "1_1") (pintype "passive"))
    )
    (net (code "78") (name "OPTO8") (class "Default")
      (node (ref "J5") (pin "3") (pinfunction "3_3") (pintype "passive"))
      (node (ref "OPTO8") (pin "1") (pinfunction "1_1") (pintype "passive"))
    )
    (net (code "79") (name "OPTO9") (class "Default")
      (node (ref "J5") (pin "2") (pinfunction "2_2") (pintype "passive"))
      (node (ref "OPTO9") (pin "1") (pinfunction "1_1") (pintype "passive"))
    )
    (net (code "80") (name "RB") (class "Default")
      (node (ref "J2") (pin "10") (pinfunction "10_10") (pintype "passive"))
      (node (ref "J5") (pin "21") (pinfunction "21_21") (pintype "passive"))
    )
    (net (code "81") (name "RVX") (class "Default")
      (node (ref "J2") (pin "4") (pinfunction "4_4") (pintype "passive"))
      (node (ref "J4") (pin "27") (pinfunction "27_27") (pintype "passive"))
    )
    (net (code "82") (name "RVY") (class "Default")
      (node (ref "J2") (pin "6") (pinfunction "6_6") (pintype "passive"))
      (node (ref "J4") (pin "28") (pinfunction "28_28") (pintype "passive"))
    )
    (net (code "83") (name "SCK") (class "Default")
      (node (ref "J6") (pin "2") (pinfunction "2_2") (pintype "passive"))
      (node (ref "U$7") (pin "P$12") (pinfunction "SCK_P$12") (pintype "bidirectional"))
    )
    (net (code "84") (name "SERVO") (class "Default")
      (node (ref "J5") (pin "27") (pinfunction "27_27") (pintype "passive"))
      (node (ref "SVM") (pin "1") (pinfunction "1_1") (pintype "passive"))
    )
    (net (code "85") (name "SS") (class "Default")
      (node (ref "J7") (pin "2") (pinfunction "2_2") (pintype "passive"))
      (node (ref "U$7") (pin "P$16") (pinfunction "SS_P$16") (pintype "bidirectional"))
    )
    (net (code "86") (name "STEP1") (class "Default")
      (node (ref "J4") (pin "16") (pinfunction "16_16") (pintype "passive"))
      (node (ref "M1") (pin "STEP") (pinfunction "STEP_STEP") (pintype "bidirectional"))
    )
    (net (code "87") (name "STEP2") (class "Default")
      (node (ref "J4") (pin "17") (pinfunction "17_17") (pintype "passive"))
      (node (ref "M2") (pin "STEP") (pinfunction "STEP_STEP") (pintype "bidirectional"))
    )
    (net (code "88") (name "STEP3") (class "Default")
      (node (ref "J4") (pin "21") (pinfunction "21_21") (pintype "passive"))
      (node (ref "M3") (pin "STEP") (pinfunction "STEP_STEP") (pintype "bidirectional"))
    )
    (net (code "89") (name "STEP4") (class "Default")
      (node (ref "J4") (pin "23") (pinfunction "23_23") (pintype "passive"))
      (node (ref "M4") (pin "STEP") (pinfunction "STEP_STEP") (pintype "bidirectional"))
    )
    (net (code "90") (name "STEP5") (class "Default")
      (node (ref "J5") (pin "6") (pinfunction "6_6") (pintype "passive"))
      (node (ref "M5") (pin "STEP") (pinfunction "STEP_STEP") (pintype "bidirectional"))
    )
    (net (code "91") (name "STEP6") (class "Default")
      (node (ref "J5") (pin "28") (pinfunction "28_28") (pintype "passive"))
      (node (ref "M6") (pin "STEP") (pinfunction "STEP_STEP") (pintype "bidirectional"))
    )
    (net (code "92") (name "VCC") (class "Default")
      (node (ref "5V_REG") (pin "4") (pinfunction "OUT_4") (pintype "passive"))
      (node (ref "AUX5") (pin "1") (pinfunction "1_1") (pintype "bidirectional"))
      (node (ref "AUX5") (pin "3") (pinfunction "3_3") (pintype "bidirectional"))
      (node (ref "AUX5") (pin "5") (pinfunction "5_5") (pintype "bidirectional"))
      (node (ref "C8") (pin "+") (pinfunction "+_+") (pintype "passive"))
      (node (ref "D1") (pin "A") (pinfunction "A_A") (pintype "passive"))
      (node (ref "D2") (pin "C") (pinfunction "C_C") (pintype "passive"))
      (node (ref "J5") (pin "30") (pinfunction "30_30") (pintype "passive"))
      (node (ref "R1") (pin "2") (pinfunction "2_2") (pintype "passive"))
      (node (ref "R_SYSLED") (pin "2") (pinfunction "2_2") (pintype "passive"))
      (node (ref "SVM") (pin "2") (pinfunction "2_2") (pintype "passive"))
    )
    (net (code "93") (name "unconnected-(J4-Pad3)") (class "Default")
      (node (ref "J4") (pin "3") (pinfunction "3_3") (pintype "passive"))
    )
    (net (code "94") (name "unconnected-(J4-Pad4)") (class "Default")
      (node (ref "J4") (pin "4") (pinfunction "4_4") (pintype "passive"))
    )
    (net (code "95") (name "unconnected-(J4-Pad5)") (class "Default")
      (node (ref "J4") (pin "5") (pinfunction "5_5") (pintype "passive"))
    )
    (net (code "96") (name "unconnected-(J4-Pad6)") (class "Default")
      (node (ref "J4") (pin "6") (pinfunction "6_6") (pintype "passive"))
    )
    (net (code "97") (name "unconnected-(J4-Pad7)") (class "Default")
      (node (ref "J4") (pin "7") (pinfunction "7_7") (pintype "passive"))
    )
    (net (code "98") (name "unconnected-(J4-Pad8)") (class "Default")
      (node (ref "J4") (pin "8") (pinfunction "8_8") (pintype "passive"))
    )
    (net (code "99") (name "unconnected-(J4-Pad9)") (class "Default")
      (node (ref "J4") (pin "9") (pinfunction "9_9") (pintype "passive"))
    )
    (net (code "100") (name "unconnected-(J4-Pad10)") (class "Default")
      (node (ref "J4") (pin "10") (pinfunction "10_10") (pintype "passive"))
    )
    (net (code "101") (name "unconnected-(J4-Pad15)") (class "Default")
      (node (ref "J4") (pin "15") (pinfunction "15_15") (pintype "passive"))
    )
    (net (code "102") (name "unconnected-(J4-Pad18)") (class "Default")
      (node (ref "J4") (pin "18") (pinfunction "18_18") (pintype "passive"))
    )
    (net (code "103") (name "unconnected-(J4-Pad19)") (class "Default")
      (node (ref "J4") (pin "19") (pinfunction "19_19") (pintype "passive"))
    )
    (net (code "104") (name "unconnected-(J4-Pad20)") (class "Default")
      (node (ref "J4") (pin "20") (pinfunction "20_20") (pintype "passive"))
    )
    (net (code "105") (name "unconnected-(J5-Pad4)") (class "Default")
      (node (ref "J5") (pin "4") (pinfunction "4_4") (pintype "passive"))
    )
    (net (code "106") (name "unconnected-(J5-Pad5)") (class "Default")
      (node (ref "J5") (pin "5") (pinfunction "5_5") (pintype "passive"))
    )
    (net (code "107") (name "unconnected-(J5-Pad7)") (class "Default")
      (node (ref "J5") (pin "7") (pinfunction "7_7") (pintype "passive"))
    )
    (net (code "108") (name "unconnected-(J5-Pad8)") (class "Default")
      (node (ref "J5") (pin "8") (pinfunction "8_8") (pintype "passive"))
    )
    (net (code "109") (name "unconnected-(J5-Pad9)") (class "Default")
      (node (ref "J5") (pin "9") (pinfunction "9_9") (pintype "passive"))
    )
    (net (code "110") (name "unconnected-(J5-Pad10)") (class "Default")
      (node (ref "J5") (pin "10") (pinfunction "10_10") (pintype "passive"))
    )
    (net (code "111") (name "unconnected-(J5-Pad11)") (class "Default")
      (node (ref "J5") (pin "11") (pinfunction "11_11") (pintype "passive"))
    )
    (net (code "112") (name "unconnected-(J5-Pad12)") (class "Default")
      (node (ref "J5") (pin "12") (pinfunction "12_12") (pintype "passive"))
    )
    (net (code "113") (name "unconnected-(J5-Pad13)") (class "Default")
      (node (ref "J5") (pin "13") (pinfunction "13_13") (pintype "passive"))
    )
    (net (code "114") (name "unconnected-(J5-Pad14)") (class "Default")
      (node (ref "J5") (pin "14") (pinfunction "14_14") (pintype "passive"))
    )
    (net (code "115") (name "unconnected-(J5-Pad19)") (class "Default")
      (node (ref "J5") (pin "19") (pinfunction "19_19") (pintype "passive"))
    )
    (net (code "116") (name "unconnected-(J5-Pad25)") (class "Default")
      (node (ref "J5") (pin "25") (pinfunction "25_25") (pintype "passive"))
    )
    (net (code "117") (name "unconnected-(J5-Pad26)") (class "Default")
      (node (ref "J5") (pin "26") (pinfunction "26_26") (pintype "passive"))
    )
    (net (code "118") (name "unconnected-(J6-Pad3)") (class "Default")
      (node (ref "J6") (pin "3") (pinfunction "3_3") (pintype "passive"))
    )
    (net (code "119") (name "unconnected-(J7-Pad1)") (class "Default")
      (node (ref "J7") (pin "1") (pinfunction "1_1") (pintype "passive"))
    )
    (net (code "120") (name "unconnected-(U$7-DB0-PadP$7)") (class "Default")
      (node (ref "U$7") (pin "P$7") (pinfunction "DB0_P$7") (pintype "bidirectional"))
    )
    (net (code "121") (name "unconnected-(U$7-DB1-PadP$8)") (class "Default")
      (node (ref "U$7") (pin "P$8") (pinfunction "DB1_P$8") (pintype "bidirectional"))
    )
    (net (code "122") (name "unconnected-(U$7-DB2-PadP$9)") (class "Default")
      (node (ref "U$7") (pin "P$9") (pinfunction "DB2_P$9") (pintype "bidirectional"))
    )
    (net (code "123") (name "unconnected-(U$7-DB3-PadP$10)") (class "Default")
      (node (ref "U$7") (pin "P$10") (pinfunction "DB3_P$10") (pintype "bidirectional"))
    )
    (net (code "124") (name "unconnected-(U$7-DB4-PadP$11)") (class "Default")
      (node (ref "U$7") (pin "P$11") (pinfunction "DB4_P$11") (pintype "bidirectional"))
    )
    (net (code "125") (name "unconnected-(U$7-EN-PadP$6)") (class "Default")
      (node (ref "U$7") (pin "P$6") (pinfunction "EN_P$6") (pintype "bidirectional"))
    )
    (net (code "126") (name "unconnected-(U$7-MISO-PadP$13)") (class "Default")
      (node (ref "U$7") (pin "P$13") (pinfunction "MISO_P$13") (pintype "bidirectional"))
    )
    (net (code "127") (name "unconnected-(U$7-NC-PadP$15)") (class "Default")
      (node (ref "U$7") (pin "P$15") (pinfunction "NC_P$15") (pintype "bidirectional"))
    )
    (net (code "128") (name "unconnected-(U$7-NC1-PadP$3)") (class "Default")
      (node (ref "U$7") (pin "P$3") (pinfunction "NC1_P$3") (pintype "bidirectional"))
    )
    (net (code "129") (name "unconnected-(U$7-RS-PadP$4)") (class "Default")
      (node (ref "U$7") (pin "P$4") (pinfunction "RS_P$4") (pintype "bidirectional"))
    )
    (net (code "130") (name "unconnected-(U$7-R{slash}W-PadP$5)") (class "Default")
      (node (ref "U$7") (pin "P$5") (pinfunction "R/W_P$5") (pintype "bidirectional"))
    )
  )
)
